# nixie_2020_displayunit_z574_v3.net
KiCad netlist of a schematic drawn in EAGLE
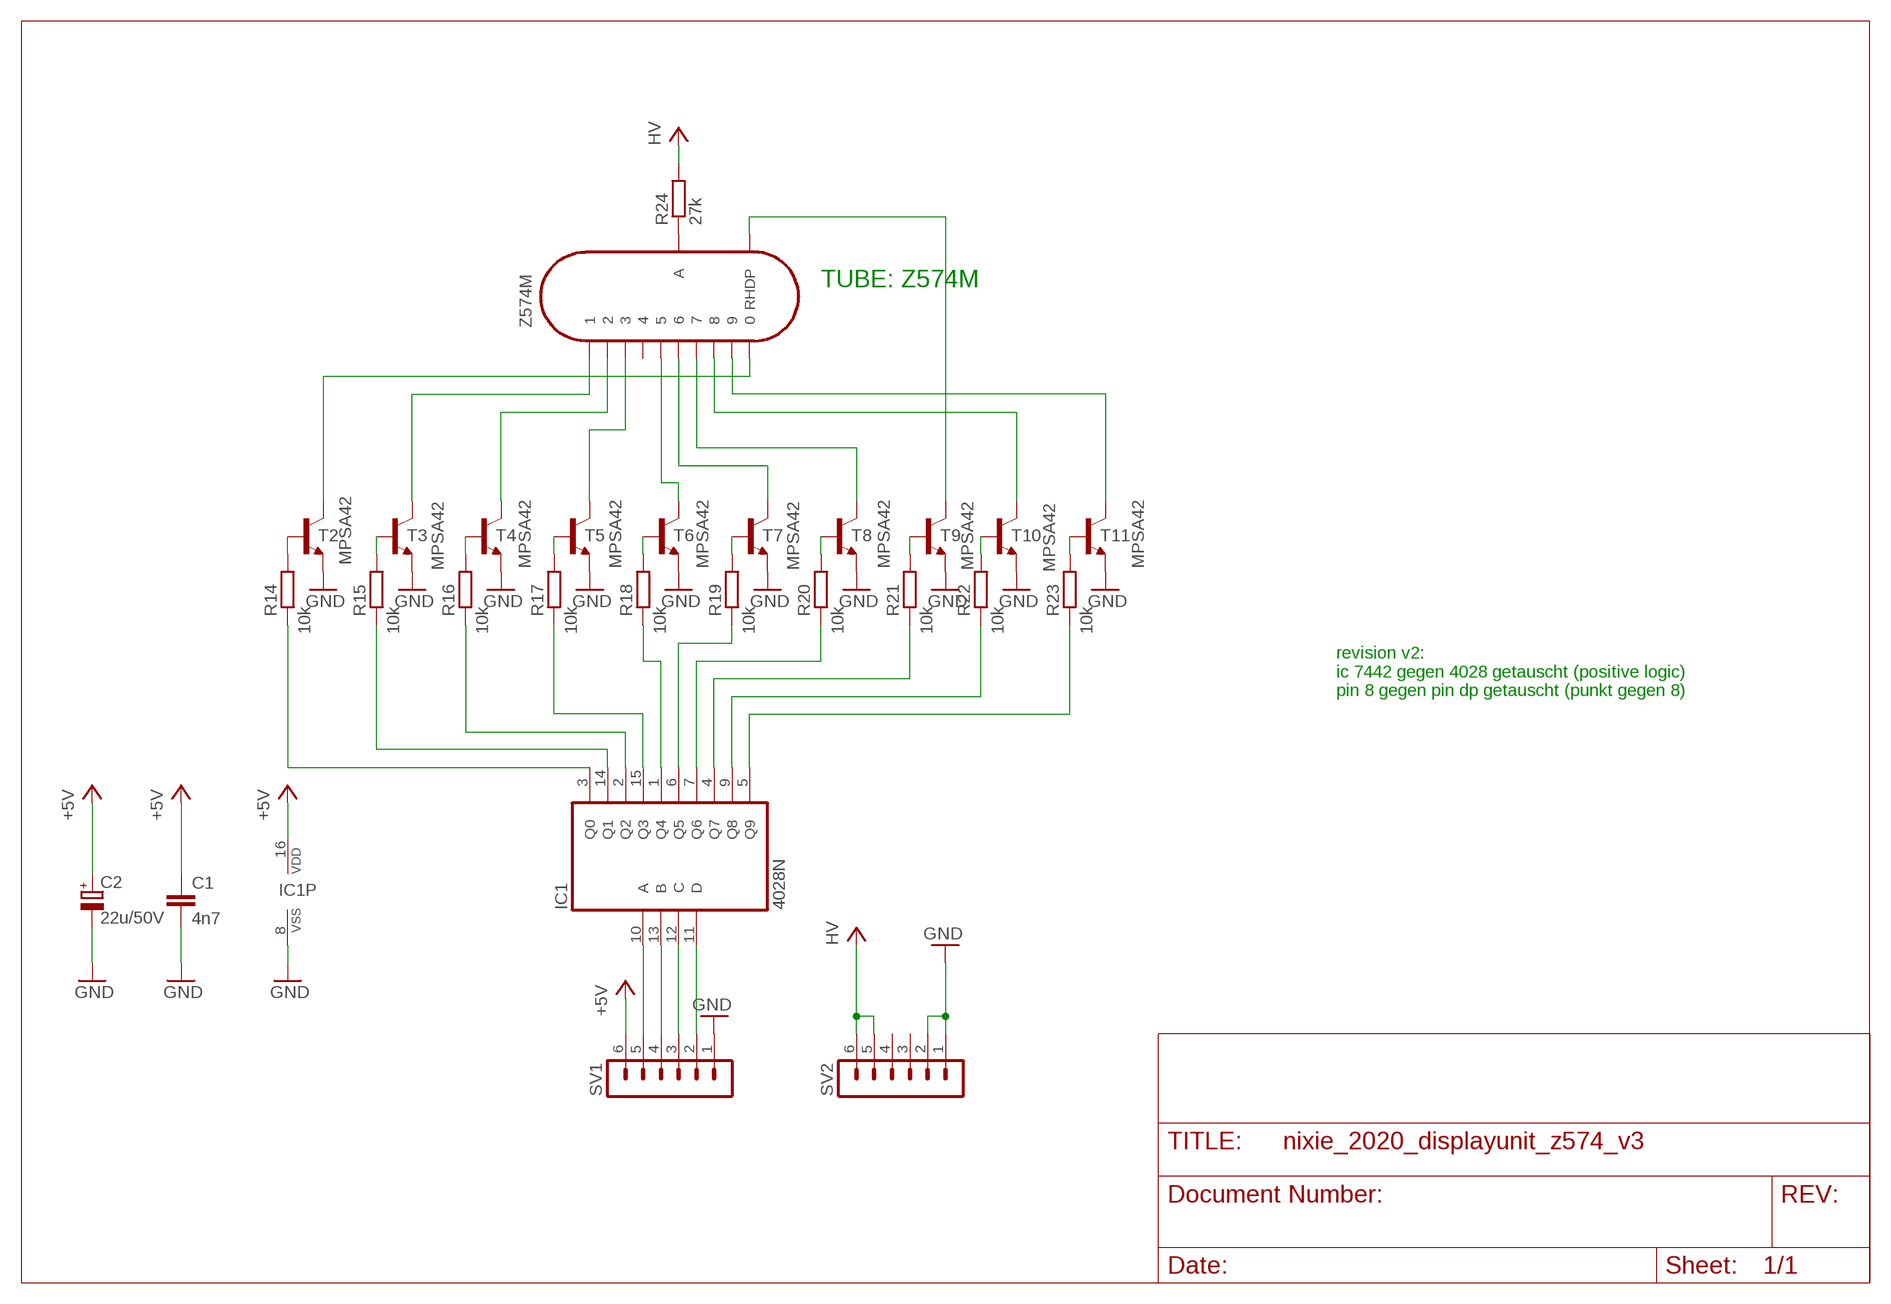
[diagram p0: schematic, sheet 1]

(export (version "E")
  (design (tool "Eeschema 10.0.6"))
  (components
    (comp (ref "C1")
      (value "4n7")
      (footprint "eagle-import:C075-032X103")
      (libsource (lib "eagle-import") (part "C-EU075-032X103"))
    )
    (comp (ref "C2")
      (value "22u/50V")
      (footprint "eagle-import:E5-5")
      (libsource (lib "eagle-import") (part "CPOL-EUE5-5"))
    )
    (comp (ref "IC1")
      (value "4028N")
      (footprint "eagle-import:DIL16")
      (libsource (lib "eagle-import") (part "4028N"))
    )
    (comp (ref "R14")
      (value "10k")
      (footprint "eagle-import:0207_10")
      (libsource (lib "eagle-import") (part "R-EU_0207/10"))
    )
    (comp (ref "R15")
      (value "10k")
      (footprint "eagle-import:0207_10")
      (libsource (lib "eagle-import") (part "R-EU_0207/10"))
    )
    (comp (ref "R16")
      (value "10k")
      (footprint "eagle-import:0207_10")
      (libsource (lib "eagle-import") (part "R-EU_0207/10"))
    )
    (comp (ref "R17")
      (value "10k")
      (footprint "eagle-import:0207_10")
      (libsource (lib "eagle-import") (part "R-EU_0207/10"))
    )
    (comp (ref "R18")
      (value "10k")
      (footprint "eagle-import:0207_10")
      (libsource (lib "eagle-import") (part "R-EU_0207/10"))
    )
    (comp (ref "R19")
      (value "10k")
      (footprint "eagle-import:0207_10")
      (libsource (lib "eagle-import") (part "R-EU_0207/10"))
    )
    (comp (ref "R20")
      (value "10k")
      (footprint "eagle-import:0207_10")
      (libsource (lib "eagle-import") (part "R-EU_0207/10"))
    )
    (comp (ref "R21")
      (value "10k")
      (footprint "eagle-import:0207_10")
      (libsource (lib "eagle-import") (part "R-EU_0207/10"))
    )
    (comp (ref "R22")
      (value "10k")
      (footprint "eagle-import:0207_10")
      (libsource (lib "eagle-import") (part "R-EU_0207/10"))
    )
    (comp (ref "R23")
      (value "10k")
      (footprint "eagle-import:0207_10")
      (libsource (lib "eagle-import") (part "R-EU_0207/10"))
    )
    (comp (ref "R24")
      (value "27k")
      (footprint "eagle-import:0207_10")
      (libsource (lib "eagle-import") (part "R-EU_0207/10"))
    )
    (comp (ref "SV1")
      (value "MA06-1")
      (footprint "eagle-import:MA06-1")
      (libsource (lib "eagle-import") (part "MA06-1"))
    )
    (comp (ref "SV2")
      (value "MA06-1")
      (footprint "eagle-import:MA06-1")
      (libsource (lib "eagle-import") (part "MA06-1"))
    )
    (comp (ref "T2")
      (value "MPSA42")
      (footprint "eagle-import:TO92-EBC")
      (libsource (lib "eagle-import") (part "-NPN-TO92-EBCMPSA42"))
    )
    (comp (ref "T3")
      (value "MPSA42")
      (footprint "eagle-import:TO92-EBC")
      (libsource (lib "eagle-import") (part "-NPN-TO92-EBCMPSA42"))
    )
    (comp (ref "T4")
      (value "MPSA42")
      (footprint "eagle-import:TO92-EBC")
      (libsource (lib "eagle-import") (part "-NPN-TO92-EBCMPSA42"))
    )
    (comp (ref "T5")
      (value "MPSA42")
      (footprint "eagle-import:TO92-EBC")
      (libsource (lib "eagle-import") (part "-NPN-TO92-EBCMPSA42"))
    )
    (comp (ref "T6")
      (value "MPSA42")
      (footprint "eagle-import:TO92-EBC")
      (libsource (lib "eagle-import") (part "-NPN-TO92-EBCMPSA42"))
    )
    (comp (ref "T7")
      (value "MPSA42")
      (footprint "eagle-import:TO92-EBC")
      (libsource (lib "eagle-import") (part "-NPN-TO92-EBCMPSA42"))
    )
    (comp (ref "T8")
      (value "MPSA42")
      (footprint "eagle-import:TO92-EBC")
      (libsource (lib "eagle-import") (part "-NPN-TO92-EBCMPSA42"))
    )
    (comp (ref "T9")
      (value "MPSA42")
      (footprint "eagle-import:TO92-EBC")
      (libsource (lib "eagle-import") (part "-NPN-TO92-EBCMPSA42"))
    )
    (comp (ref "T10")
      (value "MPSA42")
      (footprint "eagle-import:TO92-EBC")
      (libsource (lib "eagle-import") (part "-NPN-TO92-EBCMPSA42"))
    )
    (comp (ref "T11")
      (value "MPSA42")
      (footprint "eagle-import:TO92-EBC")
      (libsource (lib "eagle-import") (part "-NPN-TO92-EBCMPSA42"))
    )
    (comp (ref "Z574M")
      (value "IN-8-2")
      (footprint "eagle-import:IN-8-2")
      (libsource (lib "eagle-import") (part "IN-8-2"))
    )
  )
  (nets
    (net (code "1") (name "+5V") (class "Default")
      (node (ref "C1") (pin "1") (pinfunction "1_1") (pintype "passive"))
      (node (ref "C2") (pin "+") (pinfunction "+_+") (pintype "passive"))
      (node (ref "IC1") (pin "16") (pinfunction "VDD_16") (pintype "power_in"))
      (node (ref "SV1") (pin "6") (pinfunction "6_6") (pintype "passive"))
    )
    (net (code "2") (name "GND") (class "Default")
      (node (ref "C1") (pin "2") (pinfunction "2_2") (pintype "passive"))
      (node (ref "C2") (pin "-") (pinfunction "-_-") (pintype "passive"))
      (node (ref "IC1") (pin "8") (pinfunction "VSS_8") (pintype "power_in"))
      (node (ref "SV1") (pin "1") (pinfunction "1_1") (pintype "passive"))
      (node (ref "SV2") (pin "1") (pinfunction "1_1") (pintype "passive"))
      (node (ref "SV2") (pin "2") (pinfunction "2_2") (pintype "passive"))
      (node (ref "T10") (pin "E") (pinfunction "E_E") (pintype "passive"))
      (node (ref "T11") (pin "E") (pinfunction "E_E") (pintype "passive"))
      (node (ref "T2") (pin "E") (pinfunction "E_E") (pintype "passive"))
      (node (ref "T3") (pin "E") (pinfunction "E_E") (pintype "passive"))
      (node (ref "T4") (pin "E") (pinfunction "E_E") (pintype "passive"))
      (node (ref "T5") (pin "E") (pinfunction "E_E") (pintype "passive"))
      (node (ref "T6") (pin "E") (pinfunction "E_E") (pintype "passive"))
      (node (ref "T7") (pin "E") (pinfunction "E_E") (pintype "passive"))
      (node (ref "T8") (pin "E") (pinfunction "E_E") (pintype "passive"))
      (node (ref "T9") (pin "E") (pinfunction "E_E") (pintype "passive"))
    )
    (net (code "3") (name "HV") (class "Default")
      (node (ref "R24") (pin "2") (pinfunction "2_2") (pintype "passive"))
      (node (ref "SV2") (pin "5") (pinfunction "5_5") (pintype "passive"))
      (node (ref "SV2") (pin "6") (pinfunction "6_6") (pintype "passive"))
    )
    (net (code "4") (name "Net-(IC1A-A)") (class "Default")
      (node (ref "IC1") (pin "10") (pinfunction "A_10") (pintype "input"))
      (node (ref "SV1") (pin "5") (pinfunction "5_5") (pintype "passive"))
    )
    (net (code "5") (name "Net-(IC1A-B)") (class "Default")
      (node (ref "IC1") (pin "13") (pinfunction "B_13") (pintype "input"))
      (node (ref "SV1") (pin "4") (pinfunction "4_4") (pintype "passive"))
    )
    (net (code "6") (name "Net-(IC1A-C)") (class "Default")
      (node (ref "IC1") (pin "12") (pinfunction "C_12") (pintype "input"))
      (node (ref "SV1") (pin "3") (pinfunction "3_3") (pintype "passive"))
    )
    (net (code "7") (name "Net-(IC1A-D)") (class "Default")
      (node (ref "IC1") (pin "11") (pinfunction "D_11") (pintype "input"))
      (node (ref "SV1") (pin "2") (pinfunction "2_2") (pintype "passive"))
    )
    (net (code "8") (name "Net-(IC1A-Q0)") (class "Default")
      (node (ref "IC1") (pin "3") (pinfunction "Q0_3") (pintype "output"))
      (node (ref "R14") (pin "1") (pinfunction "1_1") (pintype "passive"))
    )
    (net (code "9") (name "Net-(IC1A-Q1)") (class "Default")
      (node (ref "IC1") (pin "14") (pinfunction "Q1_14") (pintype "output"))
      (node (ref "R15") (pin "1") (pinfunction "1_1") (pintype "passive"))
    )
    (net (code "10") (name "Net-(IC1A-Q2)") (class "Default")
      (node (ref "IC1") (pin "2") (pinfunction "Q2_2") (pintype "output"))
      (node (ref "R16") (pin "1") (pinfunction "1_1") (pintype "passive"))
    )
    (net (code "11") (name "Net-(IC1A-Q3)") (class "Default")
      (node (ref "IC1") (pin "15") (pinfunction "Q3_15") (pintype "output"))
      (node (ref "R17") (pin "1") (pinfunction "1_1") (pintype "passive"))
    )
    (net (code "12") (name "Net-(IC1A-Q4)") (class "Default")
      (node (ref "IC1") (pin "1") (pinfunction "Q4_1") (pintype "output"))
      (node (ref "R18") (pin "1") (pinfunction "1_1") (pintype "passive"))
    )
    (net (code "13") (name "Net-(IC1A-Q5)") (class "Default")
      (node (ref "IC1") (pin "6") (pinfunction "Q5_6") (pintype "output"))
      (node (ref "R19") (pin "1") (pinfunction "1_1") (pintype "passive"))
    )
    (net (code "14") (name "Net-(IC1A-Q6)") (class "Default")
      (node (ref "IC1") (pin "7") (pinfunction "Q6_7") (pintype "output"))
      (node (ref "R20") (pin "1") (pinfunction "1_1") (pintype "passive"))
    )
    (net (code "15") (name "Net-(IC1A-Q7)") (class "Default")
      (node (ref "IC1") (pin "4") (pinfunction "Q7_4") (pintype "output"))
      (node (ref "R21") (pin "1") (pinfunction "1_1") (pintype "passive"))
    )
    (net (code "16") (name "Net-(IC1A-Q8)") (class "Default")
      (node (ref "IC1") (pin "9") (pinfunction "Q8_9") (pintype "output"))
      (node (ref "R22") (pin "1") (pinfunction "1_1") (pintype "passive"))
    )
    (net (code "17") (name "Net-(IC1A-Q9)") (class "Default")
      (node (ref "IC1") (pin "5") (pinfunction "Q9_5") (pintype "output"))
      (node (ref "R23") (pin "1") (pinfunction "1_1") (pintype "passive"))
    )
    (net (code "18") (name "Net-(R14-Pad2)") (class "Default")
      (node (ref "R14") (pin "2") (pinfunction "2_2") (pintype "passive"))
      (node (ref "T2") (pin "B") (pinfunction "B_B") (pintype "passive"))
    )
    (net (code "19") (name "Net-(R15-Pad2)") (class "Default")
      (node (ref "R15") (pin "2") (pinfunction "2_2") (pintype "passive"))
      (node (ref "T3") (pin "B") (pinfunction "B_B") (pintype "passive"))
    )
    (net (code "20") (name "Net-(R16-Pad2)") (class "Default")
      (node (ref "R16") (pin "2") (pinfunction "2_2") (pintype "passive"))
      (node (ref "T4") (pin "B") (pinfunction "B_B") (pintype "passive"))
    )
    (net (code "21") (name "Net-(R17-Pad2)") (class "Default")
      (node (ref "R17") (pin "2") (pinfunction "2_2") (pintype "passive"))
      (node (ref "T5") (pin "B") (pinfunction "B_B") (pintype "passive"))
    )
    (net (code "22") (name "Net-(R18-Pad2)") (class "Default")
      (node (ref "R18") (pin "2") (pinfunction "2_2") (pintype "passive"))
      (node (ref "T6") (pin "B") (pinfunction "B_B") (pintype "passive"))
    )
    (net (code "23") (name "Net-(R19-Pad2)") (class "Default")
      (node (ref "R19") (pin "2") (pinfunction "2_2") (pintype "passive"))
      (node (ref "T7") (pin "B") (pinfunction "B_B") (pintype "passive"))
    )
    (net (code "24") (name "Net-(R20-Pad2)") (class "Default")
      (node (ref "R20") (pin "2") (pinfunction "2_2") (pintype "passive"))
      (node (ref "T8") (pin "B") (pinfunction "B_B") (pintype "passive"))
    )
    (net (code "25") (name "Net-(R21-Pad2)") (class "Default")
      (node (ref "R21") (pin "2") (pinfunction "2_2") (pintype "passive"))
      (node (ref "T9") (pin "B") (pinfunction "B_B") (pintype "passive"))
    )
    (net (code "26") (name "Net-(R22-Pad2)") (class "Default")
      (node (ref "R22") (pin "2") (pinfunction "2_2") (pintype "passive"))
      (node (ref "T10") (pin "B") (pinfunction "B_B") (pintype "passive"))
    )
    (net (code "27") (name "Net-(R23-Pad2)") (class "Default")
      (node (ref "R23") (pin "2") (pinfunction "2_2") (pintype "passive"))
      (node (ref "T11") (pin "B") (pinfunction "B_B") (pintype "passive"))
    )
    (net (code "28") (name "Net-(R24-Pad1)") (class "Default")
      (node (ref "R24") (pin "1") (pinfunction "1_1") (pintype "passive"))
      (node (ref "Z574M") (pin "A") (pinfunction "A_A") (pintype "bidirectional"))
    )
    (net (code "29") (name "Net-(T2-PadC)") (class "Default")
      (node (ref "T2") (pin "C") (pinfunction "C_C") (pintype "passive"))
      (node (ref "Z574M") (pin "0") (pinfunction "0_0") (pintype "bidirectional"))
    )
    (net (code "30") (name "Net-(T3-PadC)") (class "Default")
      (node (ref "T3") (pin "C") (pinfunction "C_C") (pintype "passive"))
      (node (ref "Z574M") (pin "1") (pinfunction "1_1") (pintype "bidirectional"))
    )
    (net (code "31") (name "Net-(T4-PadC)") (class "Default")
      (node (ref "T4") (pin "C") (pinfunction "C_C") (pintype "passive"))
      (node (ref "Z574M") (pin "2") (pinfunction "2_2") (pintype "bidirectional"))
    )
    (net (code "32") (name "Net-(T5-PadC)") (class "Default")
      (node (ref "T5") (pin "C") (pinfunction "C_C") (pintype "passive"))
      (node (ref "Z574M") (pin "3") (pinfunction "3_3") (pintype "bidirectional"))
    )
    (net (code "33") (name "Net-(T6-PadC)") (class "Default")
      (node (ref "T6") (pin "C") (pinfunction "C_C") (pintype "passive"))
      (node (ref "Z574M") (pin "5") (pinfunction "5_5") (pintype "bidirectional"))
    )
    (net (code "34") (name "Net-(T7-PadC)") (class "Default")
      (node (ref "T7") (pin "C") (pinfunction "C_C") (pintype "passive"))
      (node (ref "Z574M") (pin "6") (pinfunction "6_6") (pintype "bidirectional"))
    )
    (net (code "35") (name "Net-(T8-PadC)") (class "Default")
      (node (ref "T8") (pin "C") (pinfunction "C_C") (pintype "passive"))
      (node (ref "Z574M") (pin "7") (pinfunction "7_7") (pintype "bidirectional"))
    )
    (net (code "36") (name "Net-(T10-PadC)") (class "Default")
      (node (ref "T10") (pin "C") (pinfunction "C_C") (pintype "passive"))
      (node (ref "Z574M") (pin "8") (pinfunction "8_8") (pintype "bidirectional"))
    )
    (net (code "37") (name "Net-(T11-PadC)") (class "Default")
      (node (ref "T11") (pin "C") (pinfunction "C_C") (pintype "passive"))
      (node (ref "Z574M") (pin "9") (pinfunction "9_9") (pintype "bidirectional"))
    )
    (net (code "38") (name "Net-(Z574M-RHDP)") (class "Default")
      (node (ref "T9") (pin "C") (pinfunction "C_C") (pintype "passive"))
      (node (ref "Z574M") (pin ".") (pinfunction "RHDP_.") (pintype "bidirectional"))
    )
    (net (code "39") (name "unconnected-(SV2-Pad3)") (class "Default")
      (node (ref "SV2") (pin "3") (pinfunction "3_3") (pintype "passive"))
    )
    (net (code "40") (name "unconnected-(SV2-Pad4)") (class "Default")
      (node (ref "SV2") (pin "4") (pinfunction "4_4") (pintype "passive"))
    )
    (net (code "41") (name "unconnected-(Z574M-Pad4)") (class "Default")
      (node (ref "Z574M") (pin "4") (pinfunction "4_4") (pintype "bidirectional"))
    )
  )
)
